# Power.net
KiCad netlist of a schematic drawn in Altium Designer
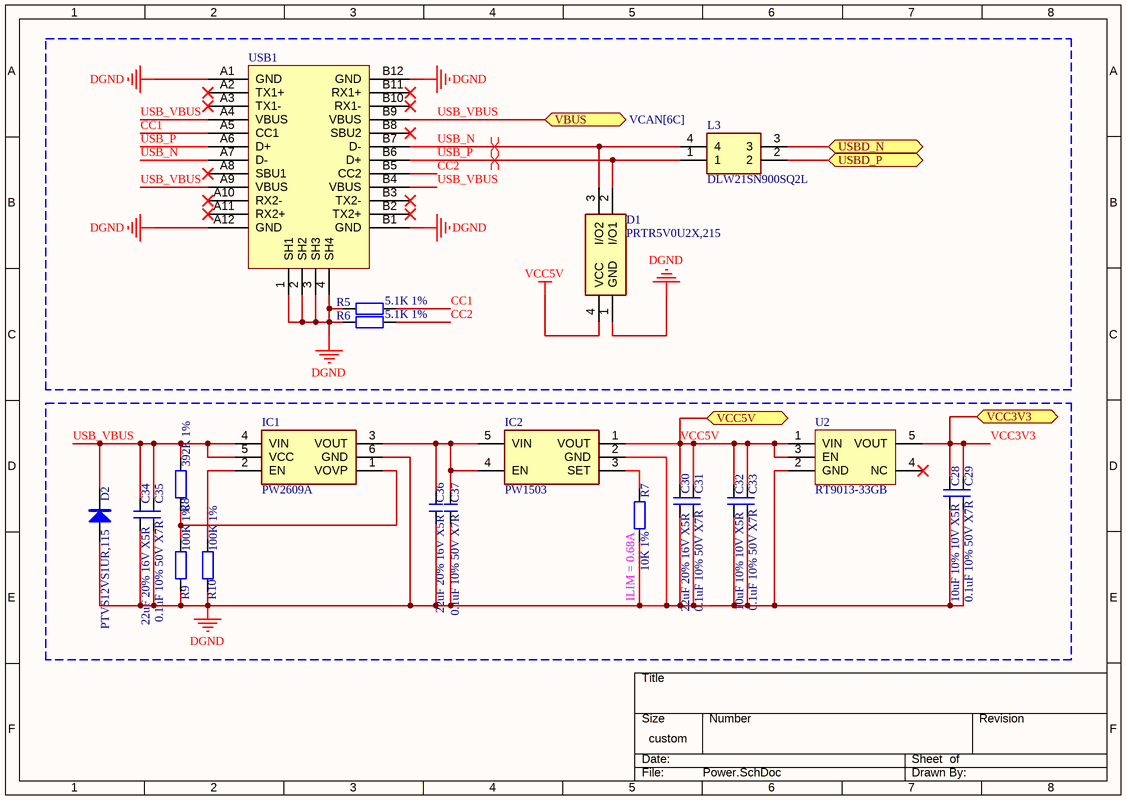
[diagram p0: Power.SchDoc]

(export (version "E")
  (design (tool "Eeschema 10.0.6"))
  (components
    (comp (ref "C28")
      (value "10uF 10% 10V X5R")
      (footprint "C 0603_L")
      (description "贴片电容")
      (libsource (lib "0.1 - 电阻-电容-电感") (part "C"))
    )
    (comp (ref "C29")
      (value "0.1uF 10% 50V X7R")
      (footprint "C 0603_L")
      (description "贴片电容")
      (libsource (lib "0.1 - 电阻-电容-电感") (part "C"))
    )
    (comp (ref "C30")
      (value "22uF 20% 16V X5R")
      (footprint "C 0603_L")
      (description "贴片电容")
      (libsource (lib "0.1 - 电阻-电容-电感") (part "C"))
    )
    (comp (ref "C31")
      (value "0.1uF 10% 50V X7R")
      (footprint "C 0603_L")
      (description "贴片电容")
      (libsource (lib "0.1 - 电阻-电容-电感") (part "C"))
    )
    (comp (ref "C32")
      (value "10uF 10% 10V X5R")
      (footprint "C 0603_L")
      (description "贴片电容")
      (libsource (lib "0.1 - 电阻-电容-电感") (part "C"))
    )
    (comp (ref "C33")
      (value "0.1uF 10% 50V X7R")
      (footprint "C 0603_L")
      (description "贴片电容")
      (libsource (lib "0.1 - 电阻-电容-电感") (part "C"))
    )
    (comp (ref "C34")
      (value "22uF 20% 16V X5R")
      (footprint "C 0603_L")
      (description "贴片电容")
      (libsource (lib "0.1 - 电阻-电容-电感") (part "C"))
    )
    (comp (ref "C35")
      (value "0.1uF 10% 50V X7R")
      (footprint "C 0603_L")
      (description "贴片电容")
      (libsource (lib "0.1 - 电阻-电容-电感") (part "C"))
    )
    (comp (ref "C36")
      (value "22uF 20% 16V X5R")
      (footprint "C 0603_L")
      (description "贴片电容")
      (libsource (lib "0.1 - 电阻-电容-电感") (part "C"))
    )
    (comp (ref "C37")
      (value "0.1uF 10% 50V X7R")
      (footprint "C 0603_L")
      (description "贴片电容")
      (libsource (lib "0.1 - 电阻-电容-电感") (part "C"))
    )
    (comp (ref "D1")
      (value "PRTR5V0U2X,215")
      (footprint "SOT-143")
      (description "Diode")
      (fields (field (name "MOUSER PART NUMBER") "771-PRTR5V0U2X-T/R"))
      (libsource (lib "mx_pcb_library") (part "PRTR5V0U2X,215"))
    )
    (comp (ref "D2")
      (value "PTVS12VS1UR,115")
      (footprint "SOD-123")
      (description "整流二极管")
      (libsource (lib "0.2 -  二极管-整流桥") (part "1N4007"))
    )
    (comp (ref "IC1")
      (value "PW2609A")
      (footprint "SOT-23-6")
      (description "Integrated Circuit")
      (fields (field (name "MANUFACTURER_PART_NUMBER") "MT9700"))
      (libsource (lib "mx_pcb_library") (part "PW2609A"))
    )
    (comp (ref "IC2")
      (value "PW1503")
      (footprint "SOT23-5")
      (description "Integrated Circuit")
      (fields (field (name "MANUFACTURER_PART_NUMBER") "MT9700"))
      (libsource (lib "mx_pcb_library") (part "MT9700"))
    )
    (comp (ref "L3")
      (value "DLW21SN900SQ2L")
      (footprint "mx_pcb_library:DLW21SN121HQ2L")
      (description "Inductor")
      (fields (field (name "MOUSER PART NUMBER") "81-DLW21SN900SQ2L"))
      (libsource (lib "mx_pcb_library") (part "DLW21SN900SQ2L"))
    )
    (comp (ref "R5")
      (value "5.1K 1%")
      (footprint "R 0603_L")
      (description "贴片电阻")
      (libsource (lib "0.1 - 电阻-电容-电感") (part "R"))
    )
    (comp (ref "R6")
      (value "5.1K 1%")
      (footprint "R 0603_L")
      (description "贴片电阻")
      (libsource (lib "0.1 - 电阻-电容-电感") (part "R"))
    )
    (comp (ref "R7")
      (value "10K 1%")
      (footprint "R 0603_L")
      (description "贴片电阻")
      (libsource (lib "0.1 - 电阻-电容-电感") (part "R"))
    )
    (comp (ref "R8")
      (value "392K 1%")
      (footprint "R 0603_L")
      (description "贴片电阻")
      (libsource (lib "0.1 - 电阻-电容-电感") (part "R"))
    )
    (comp (ref "R9")
      (value "100K 1%")
      (footprint "R 0603_L")
      (description "贴片电阻")
      (libsource (lib "0.1 - 电阻-电容-电感") (part "R"))
    )
    (comp (ref "R10")
      (value "100K 1%")
      (footprint "R 0603_L")
      (description "贴片电阻")
      (libsource (lib "0.1 - 电阻-电容-电感") (part "R"))
    )
    (comp (ref "U2")
      (value "RT9013-33GB")
      (footprint "SOT23-5M")
      (libsource (lib "mx_pcb_library") (part "RT9013-33GB"))
    )
    (comp (ref "USB1")
      (value "~")
      (footprint "Type-C-TOP")
      (libsource (lib "mx_pcb_library") (part "USB_Type-C"))
    )
  )
  (nets
    (net (code "1") (name "/CC1") (class "Default")
      (node (ref "R5") (pin "2") (pinfunction "2_2") (pintype "passive"))
      (node (ref "USB1") (pin "A5") (pinfunction "CC1_A5") (pintype "passive"))
    )
    (net (code "2") (name "/CC2") (class "Default")
      (node (ref "R6") (pin "2") (pinfunction "2_2") (pintype "passive"))
      (node (ref "USB1") (pin "B5") (pinfunction "CC2_B5") (pintype "passive"))
    )
    (net (code "3") (name "/USBD_N") (class "Default")
      (node (ref "L3") (pin "3") (pinfunction "3_3") (pintype "passive"))
    )
    (net (code "4") (name "/USBD_P") (class "Default")
      (node (ref "L3") (pin "2") (pinfunction "2_2") (pintype "passive"))
    )
    (net (code "5") (name "/USB_N") (class "Default")
      (node (ref "D1") (pin "3") (pinfunction "I/O2_3") (pintype "passive"))
      (node (ref "L3") (pin "4") (pinfunction "4_4") (pintype "passive"))
      (node (ref "USB1") (pin "A7") (pinfunction "D-_A7") (pintype "passive"))
      (node (ref "USB1") (pin "B7") (pinfunction "D-_B7") (pintype "passive"))
    )
    (net (code "6") (name "/USB_P") (class "Default")
      (node (ref "D1") (pin "2") (pinfunction "I/O1_2") (pintype "passive"))
      (node (ref "L3") (pin "1") (pinfunction "1_1") (pintype "passive"))
      (node (ref "USB1") (pin "A6") (pinfunction "D+_A6") (pintype "passive"))
      (node (ref "USB1") (pin "B6") (pinfunction "D+_B6") (pintype "passive"))
    )
    (net (code "7") (name "/USB_VBUS") (class "Default")
      (node (ref "C34") (pin "2") (pinfunction "2_2") (pintype "passive"))
      (node (ref "C35") (pin "2") (pinfunction "2_2") (pintype "passive"))
      (node (ref "D2") (pin "2") (pinfunction "K_2") (pintype "passive"))
      (node (ref "IC1") (pin "4") (pinfunction "VIN_4") (pintype "passive"))
      (node (ref "IC1") (pin "5") (pinfunction "VCC_5") (pintype "passive"))
      (node (ref "R8") (pin "1") (pinfunction "1_1") (pintype "passive"))
      (node (ref "USB1") (pin "A4") (pinfunction "VBUS_A4") (pintype "passive"))
      (node (ref "USB1") (pin "A9") (pinfunction "VBUS_A9") (pintype "passive"))
      (node (ref "USB1") (pin "B4") (pinfunction "VBUS_B4") (pintype "passive"))
      (node (ref "USB1") (pin "B9") (pinfunction "VBUS_B9") (pintype "passive"))
    )
    (net (code "8") (name "/VCC3V3") (class "Default")
      (node (ref "C28") (pin "1") (pinfunction "1_1") (pintype "passive"))
      (node (ref "C29") (pin "1") (pinfunction "1_1") (pintype "passive"))
      (node (ref "U2") (pin "5") (pinfunction "VOUT_5") (pintype "passive"))
    )
    (net (code "9") (name "DGND") (class "Default")
      (node (ref "C28") (pin "2") (pinfunction "2_2") (pintype "passive"))
      (node (ref "C29") (pin "2") (pinfunction "2_2") (pintype "passive"))
      (node (ref "C30") (pin "1") (pinfunction "1_1") (pintype "passive"))
      (node (ref "C31") (pin "2") (pinfunction "2_2") (pintype "passive"))
      (node (ref "C32") (pin "2") (pinfunction "2_2") (pintype "passive"))
      (node (ref "C33") (pin "2") (pinfunction "2_2") (pintype "passive"))
      (node (ref "C34") (pin "1") (pinfunction "1_1") (pintype "passive"))
      (node (ref "C35") (pin "1") (pinfunction "1_1") (pintype "passive"))
      (node (ref "C36") (pin "1") (pinfunction "1_1") (pintype "passive"))
      (node (ref "C37") (pin "1") (pinfunction "1_1") (pintype "passive"))
      (node (ref "D1") (pin "1") (pinfunction "GND_1") (pintype "passive"))
      (node (ref "D2") (pin "1") (pinfunction "A_1") (pintype "passive"))
      (node (ref "IC1") (pin "6") (pinfunction "GND_6") (pintype "passive"))
      (node (ref "IC2") (pin "2") (pinfunction "GND_2") (pintype "passive"))
      (node (ref "R10") (pin "2") (pinfunction "2_2") (pintype "passive"))
      (node (ref "R5") (pin "1") (pinfunction "1_1") (pintype "passive"))
      (node (ref "R6") (pin "1") (pinfunction "1_1") (pintype "passive"))
      (node (ref "R7") (pin "1") (pinfunction "1_1") (pintype "passive"))
      (node (ref "R9") (pin "2") (pinfunction "2_2") (pintype "passive"))
      (node (ref "U2") (pin "2") (pinfunction "GND_2") (pintype "passive"))
      (node (ref "USB1") (pin "1") (pinfunction "SH1_1") (pintype "passive"))
      (node (ref "USB1") (pin "2") (pinfunction "SH2_2") (pintype "passive"))
      (node (ref "USB1") (pin "3") (pinfunction "SH3_3") (pintype "passive"))
      (node (ref "USB1") (pin "4") (pinfunction "SH4_4") (pintype "passive"))
      (node (ref "USB1") (pin "A1") (pinfunction "GND_A1") (pintype "passive"))
      (node (ref "USB1") (pin "A12") (pinfunction "GND_A12") (pintype "passive"))
      (node (ref "USB1") (pin "B1") (pinfunction "GND_B1") (pintype "passive"))
      (node (ref "USB1") (pin "B12") (pinfunction "GND_B12") (pintype "passive"))
    )
    (net (code "10") (name "Net-(IC1-EN)") (class "Default")
      (node (ref "IC1") (pin "2") (pinfunction "EN_2") (pintype "passive"))
      (node (ref "R10") (pin "1") (pinfunction "1_1") (pintype "passive"))
    )
    (net (code "11") (name "Net-(IC1-VOUT)") (class "Default")
      (node (ref "C36") (pin "2") (pinfunction "2_2") (pintype "passive"))
      (node (ref "C37") (pin "2") (pinfunction "2_2") (pintype "passive"))
      (node (ref "IC1") (pin "3") (pinfunction "VOUT_3") (pintype "passive"))
      (node (ref "IC2") (pin "4") (pinfunction "EN_4") (pintype "passive"))
      (node (ref "IC2") (pin "5") (pinfunction "VIN_5") (pintype "passive"))
    )
    (net (code "12") (name "Net-(IC1-VOVP)") (class "Default")
      (node (ref "IC1") (pin "1") (pinfunction "VOVP_1") (pintype "passive"))
      (node (ref "R8") (pin "2") (pinfunction "2_2") (pintype "passive"))
      (node (ref "R9") (pin "1") (pinfunction "1_1") (pintype "passive"))
    )
    (net (code "13") (name "Net-(IC2-SET)") (class "Default")
      (node (ref "IC2") (pin "3") (pinfunction "SET_3") (pintype "passive"))
      (node (ref "R7") (pin "2") (pinfunction "2_2") (pintype "passive"))
    )
    (net (code "14") (name "VCC5V") (class "Default")
      (node (ref "C30") (pin "2") (pinfunction "2_2") (pintype "passive"))
      (node (ref "C31") (pin "1") (pinfunction "1_1") (pintype "passive"))
      (node (ref "C32") (pin "1") (pinfunction "1_1") (pintype "passive"))
      (node (ref "C33") (pin "1") (pinfunction "1_1") (pintype "passive"))
      (node (ref "D1") (pin "4") (pinfunction "VCC_4") (pintype "passive"))
      (node (ref "IC2") (pin "1") (pinfunction "VOUT_1") (pintype "passive"))
      (node (ref "U2") (pin "1") (pinfunction "VIN_1") (pintype "passive"))
      (node (ref "U2") (pin "3") (pinfunction "EN_3") (pintype "passive"))
    )
    (net (code "15") (name "unconnected-(U2-NC-Pad4)") (class "Default")
      (node (ref "U2") (pin "4") (pinfunction "NC_4") (pintype "passive+no_connect"))
    )
    (net (code "16") (name "unconnected-(USB1-RX1+-PadB11)") (class "Default")
      (node (ref "USB1") (pin "B11") (pinfunction "RX1+_B11") (pintype "passive+no_connect"))
    )
    (net (code "17") (name "unconnected-(USB1-RX1--PadB10)") (class "Default")
      (node (ref "USB1") (pin "B10") (pinfunction "RX1-_B10") (pintype "passive+no_connect"))
    )
    (net (code "18") (name "unconnected-(USB1-RX2+-PadA11)") (class "Default")
      (node (ref "USB1") (pin "A11") (pinfunction "RX2+_A11") (pintype "passive+no_connect"))
    )
    (net (code "19") (name "unconnected-(USB1-RX2--PadA10)") (class "Default")
      (node (ref "USB1") (pin "A10") (pinfunction "RX2-_A10") (pintype "passive+no_connect"))
    )
    (net (code "20") (name "unconnected-(USB1-SBU1-PadA8)") (class "Default")
      (node (ref "USB1") (pin "A8") (pinfunction "SBU1_A8") (pintype "passive+no_connect"))
    )
    (net (code "21") (name "unconnected-(USB1-SBU2-PadB8)") (class "Default")
      (node (ref "USB1") (pin "B8") (pinfunction "SBU2_B8") (pintype "passive+no_connect"))
    )
    (net (code "22") (name "unconnected-(USB1-TX1+-PadA2)") (class "Default")
      (node (ref "USB1") (pin "A2") (pinfunction "TX1+_A2") (pintype "passive+no_connect"))
    )
    (net (code "23") (name "unconnected-(USB1-TX1--PadA3)") (class "Default")
      (node (ref "USB1") (pin "A3") (pinfunction "TX1-_A3") (pintype "passive+no_connect"))
    )
    (net (code "24") (name "unconnected-(USB1-TX2+-PadB2)") (class "Default")
      (node (ref "USB1") (pin "B2") (pinfunction "TX2+_B2") (pintype "passive+no_connect"))
    )
    (net (code "25") (name "unconnected-(USB1-TX2--PadB3)") (class "Default")
      (node (ref "USB1") (pin "B3") (pinfunction "TX2-_B3") (pintype "passive+no_connect"))
    )
  )
)
